# standalone.net
KiCad netlist of a schematic drawn in EAGLE
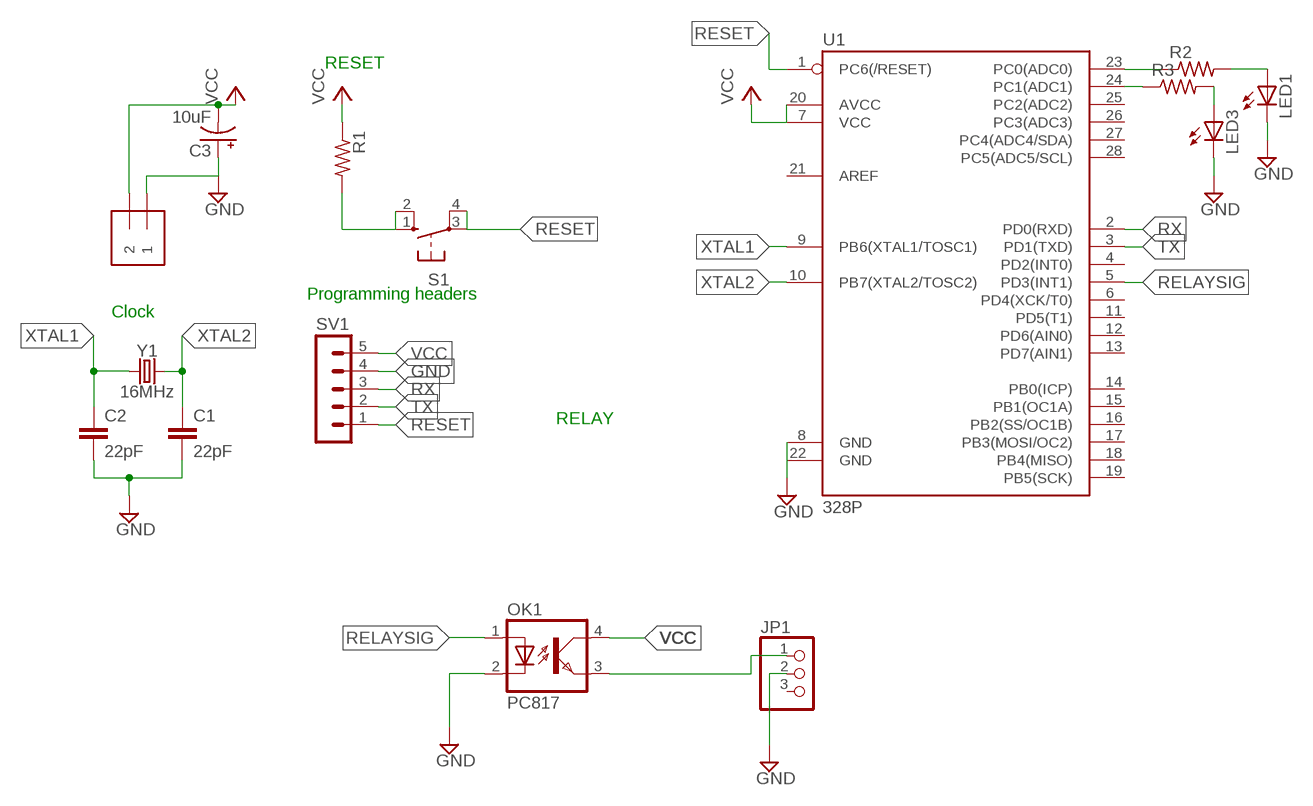
[diagram p0: schematic, sheet 1]

(export (version "E")
  (design (tool "Eeschema 10.0.6"))
  (components
    (comp (ref "C1")
      (value "22pF")
      (footprint "eagle-import:CAP-PTH-2.54")
      (libsource (lib "eagle-import") (part "22PF-PTH-2.54MM-200V-5%"))
    )
    (comp (ref "C2")
      (value "22pF")
      (footprint "eagle-import:CAP-PTH-2.54")
      (libsource (lib "eagle-import") (part "22PF-PTH-2.54MM-200V-5%"))
    )
    (comp (ref "C3")
      (value "10uF")
      (footprint "eagle-import:CPOL-RADIAL-2.5MM-5MM")
      (libsource (lib "eagle-import") (part "10UF-POLAR-RADIAL-2.5MM-25V-20%"))
    )
    (comp (ref "J1")
      (value "1X2-3.5MM")
      (footprint "eagle-import:1X2-3.5MM")
      (libsource (lib "eagle-import") (part "1X2-3.5MM"))
    )
    (comp (ref "JP1")
      (value "PINHD-1X3")
      (footprint "eagle-import:1X03")
      (libsource (lib "eagle-import") (part "PINHD-1X3"))
    )
    (comp (ref "LED1")
      (value "LED5MM")
      (footprint "eagle-import:LED5MM")
      (libsource (lib "eagle-import") (part "LED5MM"))
    )
    (comp (ref "LED3")
      (value "LED5MM")
      (footprint "eagle-import:LED5MM")
      (libsource (lib "eagle-import") (part "LED5MM"))
    )
    (comp (ref "OK1")
      (value "PC817")
      (footprint "eagle-import:DIL04")
      (fields (field (name "MPN") "PC817X4J000F"))
      (libsource (lib "eagle-import") (part "PC817"))
    )
    (comp (ref "R1")
      (value "R-US_0617/5V")
      (footprint "eagle-import:0617V")
      (libsource (lib "eagle-import") (part "R-US_0617/5V"))
    )
    (comp (ref "R2")
      (value "R-US_0204/5")
      (footprint "eagle-import:0204_5")
      (libsource (lib "eagle-import") (part "resistor_348_R-US_0204/5"))
    )
    (comp (ref "R3")
      (value "R-US_0204/7")
      (footprint "eagle-import:0204_7")
      (libsource (lib "eagle-import") (part "R-US_0204/7"))
    )
    (comp (ref "S1")
      (value "10-XX")
      (footprint "eagle-import:B3F-10XX")
      (fields (field (name "MPN") "B3F-1000"))
      (libsource (lib "eagle-import") (part "10-XX"))
    )
    (comp (ref "SV1")
      (value "MA05-1")
      (footprint "eagle-import:MA05-1")
      (libsource (lib "eagle-import") (part "MA05-1"))
    )
    (comp (ref "U1")
      (value "328P")
      (footprint "eagle-import:DIP28")
      (libsource (lib "eagle-import") (part "ATMEGA328P_PDIP"))
    )
    (comp (ref "Y1")
      (value "16MHz")
      (footprint "eagle-import:HC49US")
      (libsource (lib "eagle-import") (part "CRYSTAL-16MHZPTH-HC49US"))
    )
  )
  (nets
    (net (code "1") (name "GND") (class "Default")
      (node (ref "C1") (pin "2") (pinfunction "2_2") (pintype "passive"))
      (node (ref "C2") (pin "2") (pinfunction "2_2") (pintype "passive"))
      (node (ref "C3") (pin "1") (pinfunction "+_1") (pintype "passive"))
      (node (ref "J1") (pin "1") (pinfunction "1_1") (pintype "passive"))
      (node (ref "JP1") (pin "2") (pinfunction "2_2") (pintype "passive"))
      (node (ref "LED1") (pin "K") (pinfunction "C_K") (pintype "passive"))
      (node (ref "LED3") (pin "K") (pinfunction "C_K") (pintype "passive"))
      (node (ref "OK1") (pin "2") (pinfunction "C_2") (pintype "passive"))
      (node (ref "SV1") (pin "4") (pinfunction "4_4") (pintype "passive"))
      (node (ref "U1") (pin "22") (pinfunction "GND_22") (pintype "bidirectional"))
      (node (ref "U1") (pin "8") (pinfunction "GND_8") (pintype "bidirectional"))
    )
    (net (code "2") (name "Net-(LED1-PadA)") (class "Default")
      (node (ref "LED1") (pin "A") (pinfunction "A_A") (pintype "passive"))
      (node (ref "R2") (pin "2") (pinfunction "2_2") (pintype "passive"))
    )
    (net (code "3") (name "Net-(LED3-PadA)") (class "Default")
      (node (ref "LED3") (pin "A") (pinfunction "A_A") (pintype "passive"))
      (node (ref "R3") (pin "2") (pinfunction "2_2") (pintype "passive"))
    )
    (net (code "4") (name "Net-(OK1-EMIT)") (class "Default")
      (node (ref "JP1") (pin "1") (pinfunction "1_1") (pintype "passive"))
      (node (ref "OK1") (pin "3") (pinfunction "EMIT_3") (pintype "passive"))
    )
    (net (code "5") (name "Net-(U1-PC0(ADC0))") (class "Default")
      (node (ref "R2") (pin "1") (pinfunction "1_1") (pintype "passive"))
      (node (ref "U1") (pin "23") (pinfunction "PC0(ADC0)_23") (pintype "bidirectional"))
    )
    (net (code "6") (name "Net-(U1-PC1(ADC1))") (class "Default")
      (node (ref "R3") (pin "1") (pinfunction "1_1") (pintype "passive"))
      (node (ref "U1") (pin "24") (pinfunction "PC1(ADC1)_24") (pintype "bidirectional"))
    )
    (net (code "7") (name "RELAYSIG") (class "Default")
      (node (ref "OK1") (pin "1") (pinfunction "A_1") (pintype "passive"))
      (node (ref "U1") (pin "5") (pinfunction "PD3(INT1)_5") (pintype "bidirectional"))
    )
    (net (code "8") (name "RESET") (class "Default")
      (node (ref "R1") (pin "2") (pinfunction "2_2") (pintype "passive"))
      (node (ref "S1") (pin "1") (pinfunction "S_1") (pintype "passive"))
      (node (ref "S1") (pin "2") (pinfunction "S1_2") (pintype "passive"))
      (node (ref "S1") (pin "3") (pinfunction "P_3") (pintype "passive"))
      (node (ref "S1") (pin "4") (pinfunction "P1_4") (pintype "passive"))
      (node (ref "SV1") (pin "1") (pinfunction "1_1") (pintype "passive"))
      (node (ref "U1") (pin "1") (pinfunction "PC6(/RESET)_1") (pintype "bidirectional"))
    )
    (net (code "9") (name "RX") (class "Default")
      (node (ref "SV1") (pin "3") (pinfunction "3_3") (pintype "passive"))
      (node (ref "U1") (pin "2") (pinfunction "PD0(RXD)_2") (pintype "bidirectional"))
    )
    (net (code "10") (name "TX") (class "Default")
      (node (ref "SV1") (pin "2") (pinfunction "2_2") (pintype "passive"))
      (node (ref "U1") (pin "3") (pinfunction "PD1(TXD)_3") (pintype "bidirectional"))
    )
    (net (code "11") (name "VCC") (class "Default")
      (node (ref "C3") (pin "2") (pinfunction "-_2") (pintype "passive"))
      (node (ref "J1") (pin "2") (pinfunction "2_2") (pintype "passive"))
      (node (ref "OK1") (pin "4") (pinfunction "COL_4") (pintype "passive"))
      (node (ref "R1") (pin "1") (pinfunction "1_1") (pintype "passive"))
      (node (ref "SV1") (pin "5") (pinfunction "5_5") (pintype "passive"))
      (node (ref "U1") (pin "20") (pinfunction "AVCC_20") (pintype "bidirectional"))
      (node (ref "U1") (pin "7") (pinfunction "VCC_7") (pintype "bidirectional"))
    )
    (net (code "12") (name "XTAL1") (class "Default")
      (node (ref "C2") (pin "1") (pinfunction "1_1") (pintype "passive"))
      (node (ref "U1") (pin "9") (pinfunction "PB6(XTAL1/TOSC1)_9") (pintype "bidirectional"))
      (node (ref "Y1") (pin "1") (pinfunction "1_1") (pintype "passive"))
    )
    (net (code "13") (name "XTAL2") (class "Default")
      (node (ref "C1") (pin "1") (pinfunction "1_1") (pintype "passive"))
      (node (ref "U1") (pin "10") (pinfunction "PB7(XTAL2/TOSC2)_10") (pintype "bidirectional"))
      (node (ref "Y1") (pin "2") (pinfunction "2_2") (pintype "passive"))
    )
    (net (code "14") (name "unconnected-(JP1-Pad3)") (class "Default")
      (node (ref "JP1") (pin "3") (pinfunction "3_3") (pintype "passive"))
    )
    (net (code "15") (name "unconnected-(U1-AREF-Pad21)") (class "Default")
      (node (ref "U1") (pin "21") (pinfunction "AREF_21") (pintype "bidirectional"))
    )
    (net (code "16") (name "unconnected-(U1-PB0(ICP)-Pad14)") (class "Default")
      (node (ref "U1") (pin "14") (pinfunction "PB0(ICP)_14") (pintype "bidirectional"))
    )
    (net (code "17") (name "unconnected-(U1-PB1(OC1A)-Pad15)") (class "Default")
      (node (ref "U1") (pin "15") (pinfunction "PB1(OC1A)_15") (pintype "bidirectional"))
    )
    (net (code "18") (name "unconnected-(U1-PB2(SS{slash}OC1B)-Pad16)") (class "Default")
      (node (ref "U1") (pin "16") (pinfunction "PB2(SS/OC1B)_16") (pintype "bidirectional"))
    )
    (net (code "19") (name "unconnected-(U1-PB3(MOSI{slash}OC2)-Pad17)") (class "Default")
      (node (ref "U1") (pin "17") (pinfunction "PB3(MOSI/OC2)_17") (pintype "bidirectional"))
    )
    (net (code "20") (name "unconnected-(U1-PB4(MISO)-Pad18)") (class "Default")
      (node (ref "U1") (pin "18") (pinfunction "PB4(MISO)_18") (pintype "bidirectional"))
    )
    (net (code "21") (name "unconnected-(U1-PB5(SCK)-Pad19)") (class "Default")
      (node (ref "U1") (pin "19") (pinfunction "PB5(SCK)_19") (pintype "bidirectional"))
    )
    (net (code "22") (name "unconnected-(U1-PC2(ADC2)-Pad25)") (class "Default")
      (node (ref "U1") (pin "25") (pinfunction "PC2(ADC2)_25") (pintype "bidirectional"))
    )
    (net (code "23") (name "unconnected-(U1-PC3(ADC3)-Pad26)") (class "Default")
      (node (ref "U1") (pin "26") (pinfunction "PC3(ADC3)_26") (pintype "bidirectional"))
    )
    (net (code "24") (name "unconnected-(U1-PC4(ADC4{slash}SDA)-Pad27)") (class "Default")
      (node (ref "U1") (pin "27") (pinfunction "PC4(ADC4/SDA)_27") (pintype "bidirectional"))
    )
    (net (code "25") (name "unconnected-(U1-PC5(ADC5{slash}SCL)-Pad28)") (class "Default")
      (node (ref "U1") (pin "28") (pinfunction "PC5(ADC5/SCL)_28") (pintype "bidirectional"))
    )
    (net (code "26") (name "unconnected-(U1-PD2(INT0)-Pad4)") (class "Default")
      (node (ref "U1") (pin "4") (pinfunction "PD2(INT0)_4") (pintype "bidirectional"))
    )
    (net (code "27") (name "unconnected-(U1-PD4(XCK{slash}T0)-Pad6)") (class "Default")
      (node (ref "U1") (pin "6") (pinfunction "PD4(XCK/T0)_6") (pintype "bidirectional"))
    )
    (net (code "28") (name "unconnected-(U1-PD5(T1)-Pad11)") (class "Default")
      (node (ref "U1") (pin "11") (pinfunction "PD5(T1)_11") (pintype "bidirectional"))
    )
    (net (code "29") (name "unconnected-(U1-PD6(AIN0)-Pad12)") (class "Default")
      (node (ref "U1") (pin "12") (pinfunction "PD6(AIN0)_12") (pintype "bidirectional"))
    )
    (net (code "30") (name "unconnected-(U1-PD7(AIN1)-Pad13)") (class "Default")
      (node (ref "U1") (pin "13") (pinfunction "PD7(AIN1)_13") (pintype "bidirectional"))
    )
  )
)
